# 454_stereo_mic_Rev020003.net
KiCad netlist of a schematic drawn in EAGLE
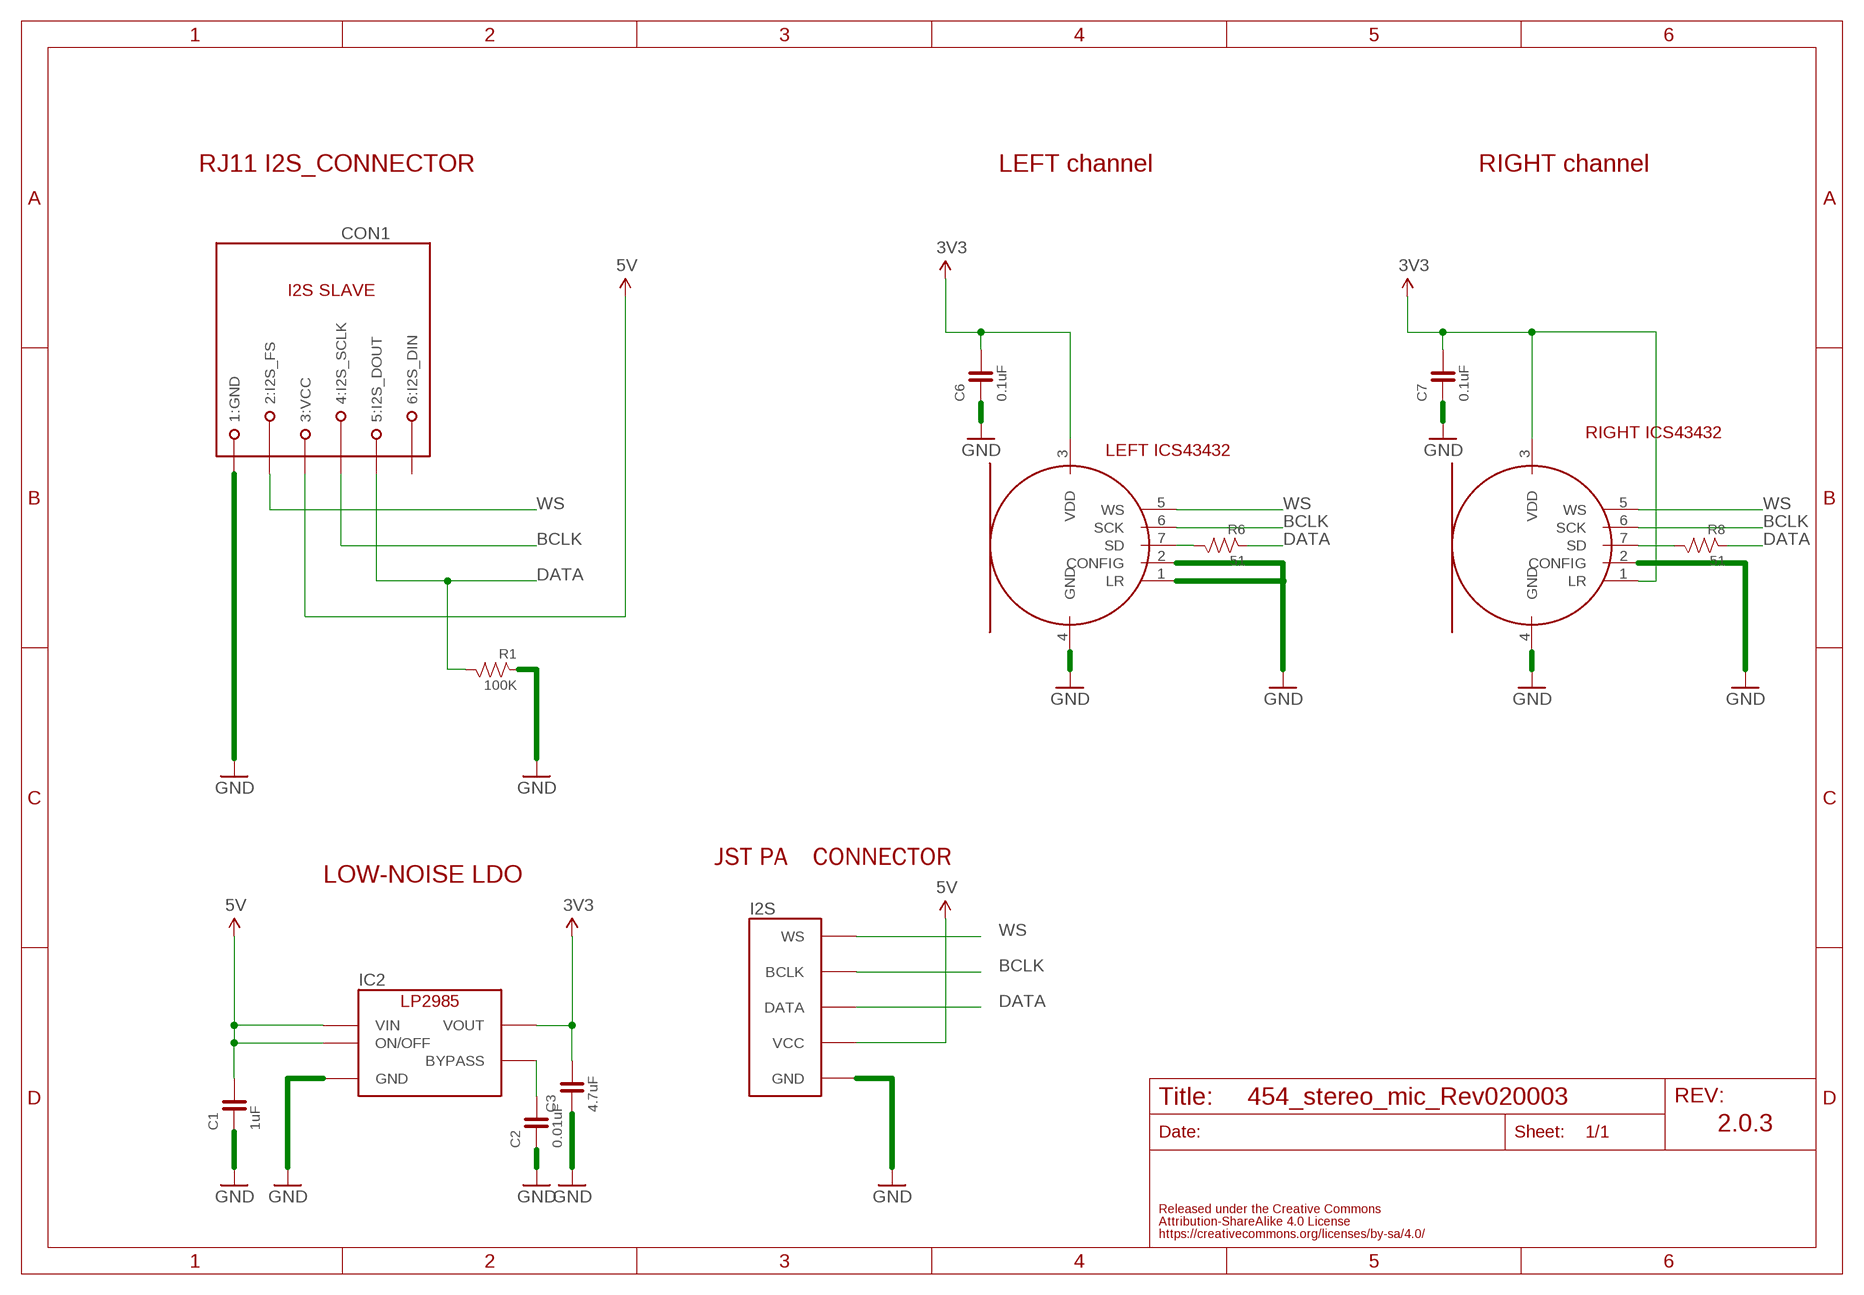
[diagram p0: schematic, sheet 1]

(export (version "E")
  (design (tool "Eeschema 10.0.6"))
  (components
    (comp (ref "C1")
      (value "1uF")
      (footprint "eagle-import:0603")
      (libsource (lib "eagle-import") (part "CAPACITOR-0603"))
    )
    (comp (ref "C2")
      (value "0.01uF")
      (footprint "eagle-import:0603")
      (libsource (lib "eagle-import") (part "CAPACITOR-0603"))
    )
    (comp (ref "C3")
      (value "4.7uF")
      (footprint "eagle-import:0603")
      (libsource (lib "eagle-import") (part "CAPACITOR-0603"))
    )
    (comp (ref "C6")
      (value "0.1uF")
      (footprint "eagle-import:0603")
      (libsource (lib "eagle-import") (part "CAPACITOR-0603"))
    )
    (comp (ref "C7")
      (value "0.1uF")
      (footprint "eagle-import:0603")
      (libsource (lib "eagle-import") (part "CAPACITOR-0603"))
    )
    (comp (ref "CON1")
      (value "MODULAR-JACK-6P-RJ11_I2S_SLAVE")
      (footprint "eagle-import:7002-6PXC-X")
      (libsource (lib "eagle-import") (part "MODULAR-JACK-6P-RJ11_I2S_SLAVE"))
    )
    (comp (ref "I2S")
      (value "FABO_BRICK_I2STOP")
      (footprint "eagle-import:FABO_BRICK_I2S_B05B-PARK-1")
      (libsource (lib "eagle-import") (part "FABO_BRICK_I2STOP"))
    )
    (comp (ref "IC2")
      (value "LP2985-33DBV")
      (footprint "eagle-import:SOT-23-5")
      (libsource (lib "eagle-import") (part "LP2985-33DBV"))
    )
    (comp (ref "MIC_LEFT")
      (value "TDK-ICS43432")
      (footprint "eagle-import:TDK-ICS43432")
      (libsource (lib "eagle-import") (part "TDK-ICS43432"))
    )
    (comp (ref "MIC_RIGHT")
      (value "TDK-ICS43432")
      (footprint "eagle-import:TDK-ICS43432")
      (libsource (lib "eagle-import") (part "TDK-ICS43432"))
    )
    (comp (ref "R1")
      (value "100K")
      (footprint "eagle-import:0603")
      (libsource (lib "eagle-import") (part "RESISTOR-0603"))
    )
    (comp (ref "R6")
      (value "51")
      (footprint "eagle-import:0603")
      (libsource (lib "eagle-import") (part "RESISTOR-0603"))
    )
    (comp (ref "R8")
      (value "51")
      (footprint "eagle-import:0603")
      (libsource (lib "eagle-import") (part "RESISTOR-0603"))
    )
  )
  (nets
    (net (code "1") (name "/BCLK") (class "Default")
      (node (ref "CON1") (pin "4") (pinfunction "4:I2S_SCLK_4") (pintype "bidirectional"))
      (node (ref "I2S") (pin "BCLK") (pinfunction "BCLK_BCLK") (pintype "bidirectional"))
      (node (ref "MIC_LEFT") (pin "6") (pinfunction "SCK_6") (pintype "bidirectional"))
      (node (ref "MIC_RIGHT") (pin "6") (pinfunction "SCK_6") (pintype "bidirectional"))
    )
    (net (code "2") (name "/DATA") (class "Default")
      (node (ref "CON1") (pin "5") (pinfunction "5:I2S_DOUT_5") (pintype "output"))
      (node (ref "I2S") (pin "DATA") (pinfunction "DATA_DATA") (pintype "bidirectional"))
      (node (ref "R1") (pin "2") (pinfunction "2_2") (pintype "bidirectional"))
      (node (ref "R6") (pin "1") (pinfunction "1_1") (pintype "bidirectional"))
      (node (ref "R8") (pin "1") (pinfunction "1_1") (pintype "bidirectional"))
    )
    (net (code "3") (name "/WS") (class "Default")
      (node (ref "CON1") (pin "2") (pinfunction "2:I2S_FS_2") (pintype "bidirectional"))
      (node (ref "I2S") (pin "WS") (pinfunction "WS_WS") (pintype "bidirectional"))
      (node (ref "MIC_LEFT") (pin "5") (pinfunction "WS_5") (pintype "bidirectional"))
      (node (ref "MIC_RIGHT") (pin "5") (pinfunction "WS_5") (pintype "bidirectional"))
    )
    (net (code "4") (name "3V3") (class "Default")
      (node (ref "C3") (pin "2") (pinfunction "2_2") (pintype "passive"))
      (node (ref "C6") (pin "2") (pinfunction "2_2") (pintype "passive"))
      (node (ref "C7") (pin "2") (pinfunction "2_2") (pintype "passive"))
      (node (ref "IC2") (pin "5") (pinfunction "VOUT_5") (pintype "output"))
      (node (ref "MIC_LEFT") (pin "3") (pinfunction "VDD_3") (pintype "bidirectional"))
      (node (ref "MIC_RIGHT") (pin "1") (pinfunction "LR_1") (pintype "bidirectional"))
      (node (ref "MIC_RIGHT") (pin "3") (pinfunction "VDD_3") (pintype "bidirectional"))
    )
    (net (code "5") (name "5V") (class "Default")
      (node (ref "C1") (pin "2") (pinfunction "2_2") (pintype "passive"))
      (node (ref "CON1") (pin "3") (pinfunction "3:VCC_3") (pintype "power_in"))
      (node (ref "I2S") (pin "VCC") (pinfunction "VCC_VCC") (pintype "bidirectional"))
      (node (ref "IC2") (pin "1") (pinfunction "VIN_1") (pintype "input"))
      (node (ref "IC2") (pin "3") (pinfunction "ON/OFF_3") (pintype "input"))
    )
    (net (code "6") (name "GND") (class "Default")
      (node (ref "C1") (pin "1") (pinfunction "1_1") (pintype "passive"))
      (node (ref "C2") (pin "1") (pinfunction "1_1") (pintype "passive"))
      (node (ref "C3") (pin "1") (pinfunction "1_1") (pintype "passive"))
      (node (ref "C6") (pin "1") (pinfunction "1_1") (pintype "passive"))
      (node (ref "C7") (pin "1") (pinfunction "1_1") (pintype "passive"))
      (node (ref "CON1") (pin "1") (pinfunction "1:GND_1") (pintype "power_in"))
      (node (ref "I2S") (pin "GND") (pinfunction "GND_GND") (pintype "bidirectional"))
      (node (ref "IC2") (pin "2") (pinfunction "GND_2") (pintype "power_in"))
      (node (ref "MIC_LEFT") (pin "1") (pinfunction "LR_1") (pintype "bidirectional"))
      (node (ref "MIC_LEFT") (pin "2") (pinfunction "CONFIG_2") (pintype "bidirectional"))
      (node (ref "MIC_LEFT") (pin "4") (pinfunction "GND_4") (pintype "bidirectional"))
      (node (ref "MIC_RIGHT") (pin "2") (pinfunction "CONFIG_2") (pintype "bidirectional"))
      (node (ref "MIC_RIGHT") (pin "4") (pinfunction "GND_4") (pintype "bidirectional"))
      (node (ref "R1") (pin "1") (pinfunction "1_1") (pintype "bidirectional"))
    )
    (net (code "7") (name "Net-(IC2-BYPASS)") (class "Default")
      (node (ref "C2") (pin "2") (pinfunction "2_2") (pintype "passive"))
      (node (ref "IC2") (pin "4") (pinfunction "BYPASS_4") (pintype "bidirectional"))
    )
    (net (code "8") (name "Net-(MIC_LEFT-SD)") (class "Default")
      (node (ref "MIC_LEFT") (pin "7") (pinfunction "SD_7") (pintype "bidirectional"))
      (node (ref "R6") (pin "2") (pinfunction "2_2") (pintype "bidirectional"))
    )
    (net (code "9") (name "Net-(MIC_RIGHT-SD)") (class "Default")
      (node (ref "MIC_RIGHT") (pin "7") (pinfunction "SD_7") (pintype "bidirectional"))
      (node (ref "R8") (pin "2") (pinfunction "2_2") (pintype "bidirectional"))
    )
    (net (code "10") (name "unconnected-(CON1-6:I2S_DIN-Pad6)") (class "Default")
      (node (ref "CON1") (pin "6") (pinfunction "6:I2S_DIN_6") (pintype "input"))
    )
  )
)
